# 03_Power.net
KiCad netlist of a schematic drawn in Altium Designer
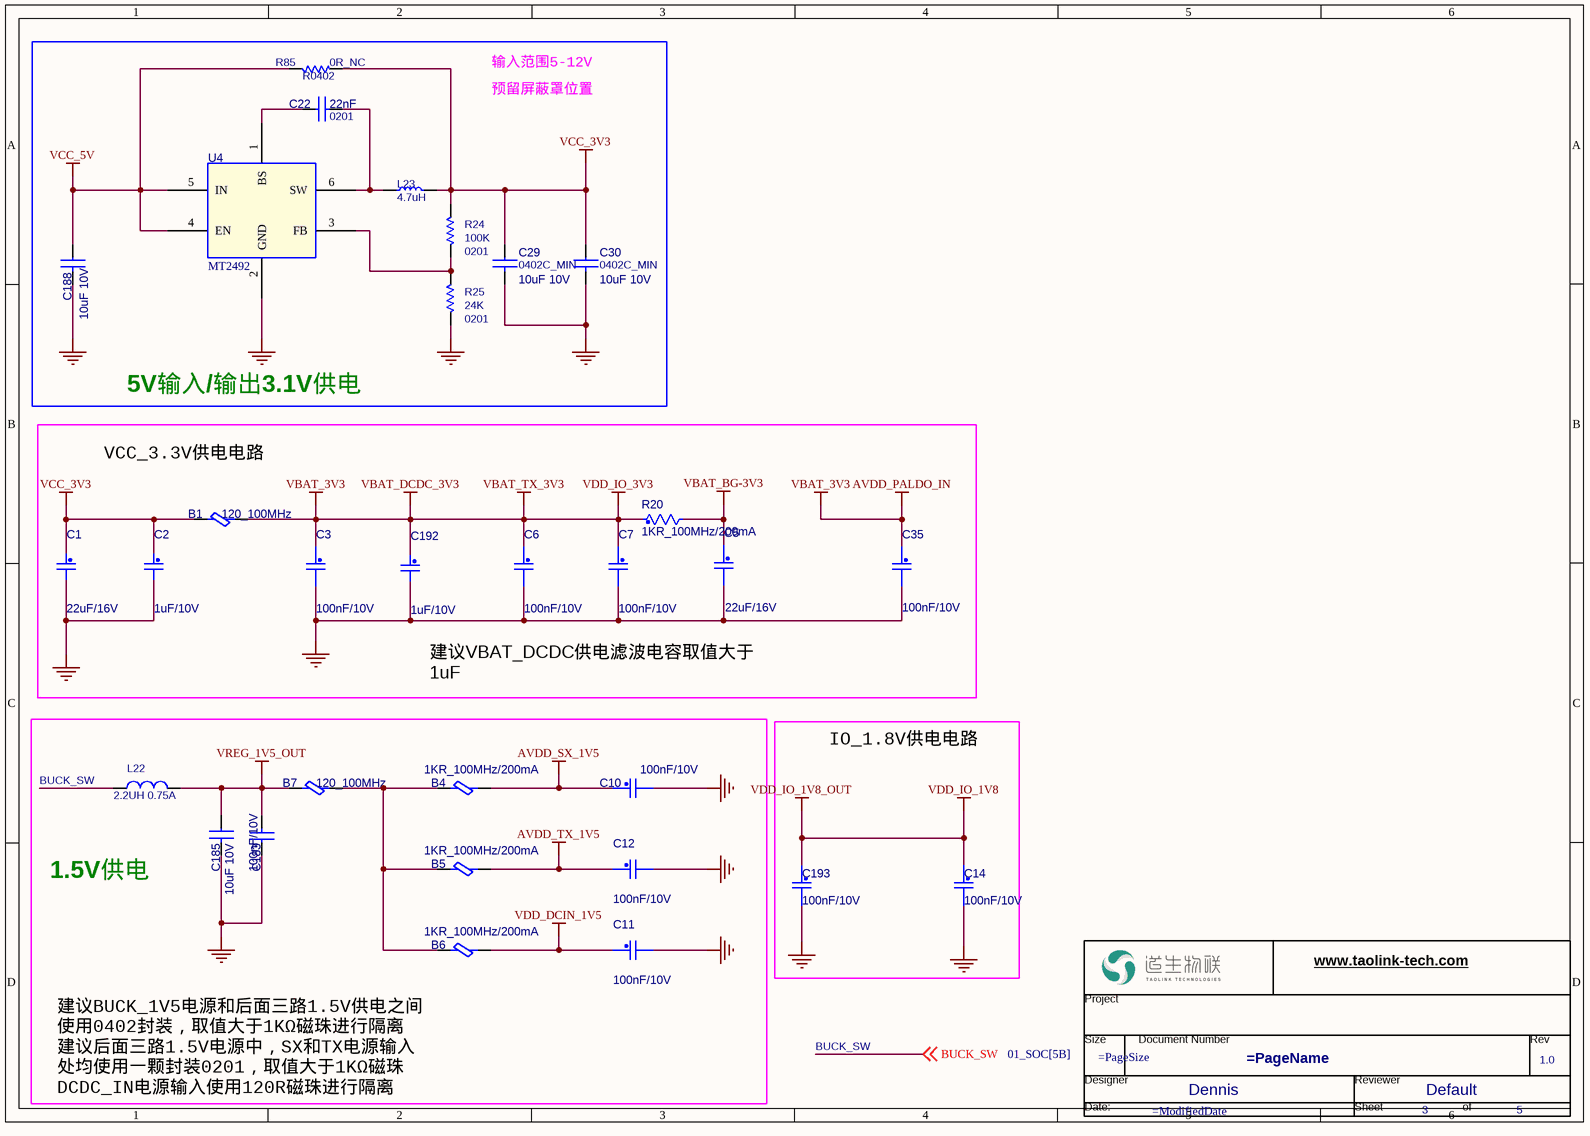
[diagram p0: 03_Power.SchDoc]

(export (version "E")
  (design (tool "Eeschema 10.0.6"))
  (components
    (comp (ref "B1")
      (value "120_100MHz")
      (footprint "l0402")
      (description "FERRITE CHIP 120 OHM 500MA 0402")
      (fields (field (name "EI PART#") "04_00075_01") (field (name "VENDOR PART#") "490-1005-1-ND"))
      (libsource (lib "*") (part "1212_BEAD_0"))
    )
    (comp (ref "B4")
      (value "1KR_100MHz/200mA")
      (footprint "0201")
      (description "FERRITE CHIP 120 OHM 500MA 0402")
      (fields (field (name "MANUFACTURE PART NUMBER") "BLM15AG121SN1D") (field (name "TOLERANCE") "25%"))
      (libsource (lib "*") (part "1212_BEAD_0"))
    )
    (comp (ref "B5")
      (value "1KR_100MHz/200mA")
      (footprint "0201")
      (description "FERRITE CHIP 120 OHM 500MA 0402")
      (fields (field (name "MANUFACTURE PART NUMBER") "BLM15AG121SN1D") (field (name "TOLERANCE") "25%"))
      (libsource (lib "*") (part "1212_BEAD_0"))
    )
    (comp (ref "B6")
      (value "1KR_100MHz/200mA")
      (footprint "0201")
      (description "FERRITE CHIP 120 OHM 500MA 0402")
      (fields (field (name "MANUFACTURE PART NUMBER") "BLM15AG121SN1D") (field (name "TOLERANCE") "25%"))
      (libsource (lib "*") (part "1212_BEAD_0"))
    )
    (comp (ref "B7")
      (value "120_100MHz")
      (footprint "l0402")
      (description "FERRITE CHIP 120 OHM 500MA 0402")
      (fields (field (name "MANUFACTURE PART NUMBER") "BLM15AG121SN1D") (field (name "TOLERANCE") "25%"))
      (libsource (lib "*") (part "1212_BEAD_0"))
    )
    (comp (ref "C1")
      (value "22uF/16V")
      (footprint "C0402")
      (description "Ceramic Capacitor, 10uF,+/-20%,X6S,16V,SMD,0603")
      (fields (field (name "MANUFACTURER") "Murata"))
      (libsource (lib "*") (part "Ceramic Capacitor"))
    )
    (comp (ref "C2")
      (value "1uF/10V")
      (footprint "0201")
      (description "Ceramic Capacitor,4.7uF 10V 0402,SUMSUNG")
      (fields (field (name "MANUFACTURER") "Samsung"))
      (libsource (lib "*") (part "Ceramic Capacitor"))
    )
    (comp (ref "C3")
      (value "100nF/10V")
      (footprint "0201")
      (description "Ceramic Capacitor,100nF,50V,+/-10%,X7R,0402,Fenghua")
      (fields (field (name "MANUFACTURER") "Fenghua"))
      (libsource (lib "*") (part "Ceramic Capacitor_14"))
    )
    (comp (ref "C5")
      (value "22uF/16V")
      (footprint "C0402")
      (description "Ceramic Capacitor,100nF,50V,+/-10%,X7R,0402,Fenghua")
      (fields (field (name "MANUFACTURER") "Fenghua"))
      (libsource (lib "*") (part "Ceramic Capacitor_14"))
    )
    (comp (ref "C6")
      (value "100nF/10V")
      (footprint "0201")
      (description "Ceramic Capacitor,100nF,50V,+/-10%,X7R,0402,Fenghua")
      (fields (field (name "MANUFACTURER") "Fenghua"))
      (libsource (lib "*") (part "Ceramic Capacitor_14"))
    )
    (comp (ref "C7")
      (value "100nF/10V")
      (footprint "0201")
      (description "Ceramic Capacitor,100nF,50V,+/-10%,X7R,0402,Fenghua")
      (fields (field (name "MANUFACTURER") "Fenghua"))
      (libsource (lib "*") (part "Ceramic Capacitor_14"))
    )
    (comp (ref "C10")
      (value "100nF/10V")
      (footprint "0201")
      (description "Ceramic Capacitor,100nF,50V,+/-10%,X7R,0402,Fenghua")
      (fields (field (name "MANUFACTURER") "Fenghua"))
      (libsource (lib "*") (part "Ceramic Capacitor_14"))
    )
    (comp (ref "C11")
      (value "100nF/10V")
      (footprint "0201")
      (description "Ceramic Capacitor,100nF,50V,+/-10%,X7R,0402,Fenghua")
      (fields (field (name "MANUFACTURER") "Fenghua"))
      (libsource (lib "*") (part "Ceramic Capacitor_14"))
    )
    (comp (ref "C12")
      (value "100nF/10V")
      (footprint "0201")
      (description "Ceramic Capacitor,100nF,50V,+/-10%,X7R,0402,Fenghua")
      (fields (field (name "MANUFACTURER") "Fenghua"))
      (libsource (lib "*") (part "Ceramic Capacitor_14"))
    )
    (comp (ref "C14")
      (value "100nF/10V")
      (footprint "0201")
      (description "Ceramic Capacitor,100nF,50V,+/-10%,X7R,0402,Fenghua")
      (fields (field (name "MANUFACTURER") "Fenghua"))
      (libsource (lib "*") (part "Ceramic Capacitor_14"))
    )
    (comp (ref "C22")
      (value "22nF")
      (footprint "0201")
      (fields (field (name "PCB FOOTPRINT") "0201"))
      (libsource (lib "*") (part "CAPACITOR NON-POL"))
    )
    (comp (ref "C29")
      (value "10uF 10V")
      (footprint "0402C_MIN")
      (fields (field (name "PCB FOOTPRINT") "0402C_MIN"))
      (libsource (lib "*") (part "CAPACITOR NON-POL"))
    )
    (comp (ref "C30")
      (value "10uF 10V")
      (footprint "0402C_MIN")
      (fields (field (name "PCB FOOTPRINT") "0402C_MIN"))
      (libsource (lib "*") (part "CAPACITOR NON-POL"))
    )
    (comp (ref "C35")
      (value "100nF/10V")
      (footprint "0201")
      (description "Ceramic Capacitor,100nF,50V,+/-10%,X7R,0402,Fenghua")
      (fields (field (name "MANUFACTURER") "Fenghua"))
      (libsource (lib "*") (part "Ceramic Capacitor_14"))
    )
    (comp (ref "C183") (value "100nF/10V") (footprint "0201") (libsource (lib "*") (part "CAP_NP")))
    (comp (ref "C185") (value "10uF 10V") (footprint "0402C_MIN") (libsource (lib "*") (part "CAP_NP")))
    (comp (ref "C188") (value "10uF 10V") (footprint "0402C_MIN") (libsource (lib "*") (part "CAP_NP")))
    (comp (ref "C192")
      (value "1uF/10V")
      (footprint "0201")
      (description "Ceramic Capacitor,4.7uF 10V 0402,SUMSUNG")
      (fields (field (name "MANUFACTURER") "Samsung"))
      (libsource (lib "*") (part "Ceramic Capacitor"))
    )
    (comp (ref "C193")
      (value "100nF/10V")
      (footprint "0201")
      (description "Ceramic Capacitor,100nF,50V,+/-10%,X7R,0402,Fenghua")
      (fields (field (name "MANUFACTURER") "Fenghua"))
      (libsource (lib "*") (part "Ceramic Capacitor_14"))
    )
    (comp (ref "L22")
      (value "2.2UH 0.75A")
      (footprint "C0603")
      (fields (field (name "REVIEWED2") "LBY"))
      (libsource (lib "*") (part "INDUCTOR_Dup2"))
    )
    (comp (ref "L23")
      (value "4.7uH")
      (footprint "R0603")
      (fields (field (name "REVIEWED") "LBY"))
      (libsource (lib "*") (part "INDUCTOR_Dup1"))
    )
    (comp (ref "R20")
      (value "1KR_100MHz/200mA")
      (footprint "0201")
      (description "Thick Film Resistor,0R,+/-5%,1/16W,-55°C ~ 155°C,SMD,0402,Fenghua")
      (fields (field (name "MANUFACTURER") "Fenghua"))
      (libsource (lib "*") (part "Resister"))
    )
    (comp (ref "R24")
      (value "100K")
      (footprint "0201")
      (fields (field (name "PCB FOOTPRINT") "0201"))
      (libsource (lib "*") (part "R"))
    )
    (comp (ref "R25")
      (value "24K")
      (footprint "0201")
      (fields (field (name "PCB FOOTPRINT") "0201"))
      (libsource (lib "*") (part "R"))
    )
    (comp (ref "R85")
      (value "0R_NC")
      (footprint "R0402")
      (fields (field (name "PCB FOOTPRINT") "R0402"))
      (libsource (lib "*") (part "R"))
    )
    (comp (ref "U4") (value "MT2492") (footprint "SOT23-6") (libsource (lib "*") (part "MT2492")))
  )
  (nets
    (net (code "1") (name "AVDD_PALDO_IN") (class "Default")
      (node (ref "B1") (pin "2") (pinfunction "2_2") (pintype "passive"))
      (node (ref "C192") (pin "1") (pinfunction "1_1") (pintype "passive"))
      (node (ref "C3") (pin "1") (pinfunction "1_1") (pintype "passive"))
      (node (ref "C35") (pin "1") (pinfunction "1_1") (pintype "passive"))
      (node (ref "C6") (pin "1") (pinfunction "1_1") (pintype "passive"))
      (node (ref "C7") (pin "1") (pinfunction "1_1") (pintype "passive"))
      (node (ref "R20") (pin "1") (pinfunction "1_1") (pintype "passive"))
    )
    (net (code "2") (name "AVDD_SX_1V5") (class "Default")
      (node (ref "B4") (pin "2") (pinfunction "2_2") (pintype "passive"))
      (node (ref "C10") (pin "1") (pinfunction "1_1") (pintype "passive"))
    )
    (net (code "3") (name "AVDD_TX_1V5") (class "Default")
      (node (ref "B5") (pin "2") (pinfunction "2_2") (pintype "passive"))
      (node (ref "C12") (pin "1") (pinfunction "1_1") (pintype "passive"))
    )
    (net (code "4") (name "BUCK_SW") (class "Default")
      (node (ref "L22") (pin "1") (pinfunction "1_1") (pintype "passive"))
    )
    (net (code "5") (name "GND") (class "Default")
      (node (ref "C1") (pin "2") (pinfunction "2_2") (pintype "passive"))
      (node (ref "C10") (pin "2") (pinfunction "2_2") (pintype "passive"))
      (node (ref "C11") (pin "2") (pinfunction "2_2") (pintype "passive"))
      (node (ref "C12") (pin "2") (pinfunction "2_2") (pintype "passive"))
      (node (ref "C14") (pin "2") (pinfunction "2_2") (pintype "passive"))
      (node (ref "C183") (pin "1") (pinfunction "1_1") (pintype "passive"))
      (node (ref "C185") (pin "2") (pinfunction "2_2") (pintype "passive"))
      (node (ref "C188") (pin "2") (pinfunction "2_2") (pintype "passive"))
      (node (ref "C192") (pin "2") (pinfunction "2_2") (pintype "passive"))
      (node (ref "C193") (pin "2") (pinfunction "2_2") (pintype "passive"))
      (node (ref "C2") (pin "2") (pinfunction "2_2") (pintype "passive"))
      (node (ref "C29") (pin "2") (pinfunction "2_2") (pintype "passive"))
      (node (ref "C3") (pin "2") (pinfunction "2_2") (pintype "passive"))
      (node (ref "C30") (pin "2") (pinfunction "2_2") (pintype "passive"))
      (node (ref "C35") (pin "2") (pinfunction "2_2") (pintype "passive"))
      (node (ref "C5") (pin "2") (pinfunction "2_2") (pintype "passive"))
      (node (ref "C6") (pin "2") (pinfunction "2_2") (pintype "passive"))
      (node (ref "C7") (pin "2") (pinfunction "2_2") (pintype "passive"))
      (node (ref "R25") (pin "2") (pinfunction "2_2") (pintype "passive"))
      (node (ref "U4") (pin "2") (pinfunction "GND_2") (pintype "passive"))
    )
    (net (code "6") (name "Net-(B4-Pad1)") (class "Default")
      (node (ref "B4") (pin "1") (pinfunction "1_1") (pintype "passive"))
      (node (ref "B5") (pin "1") (pinfunction "1_1") (pintype "passive"))
      (node (ref "B6") (pin "1") (pinfunction "1_1") (pintype "passive"))
      (node (ref "B7") (pin "2") (pinfunction "2_2") (pintype "passive"))
    )
    (net (code "7") (name "Net-(U4-BS)") (class "Default")
      (node (ref "C22") (pin "1") (pinfunction "1_1") (pintype "passive"))
      (node (ref "U4") (pin "1") (pinfunction "BS_1") (pintype "passive"))
    )
    (net (code "8") (name "Net-(U4-FB)") (class "Default")
      (node (ref "R24") (pin "2") (pinfunction "2_2") (pintype "passive"))
      (node (ref "R25") (pin "1") (pinfunction "1_1") (pintype "passive"))
      (node (ref "U4") (pin "3") (pinfunction "FB_3") (pintype "passive"))
    )
    (net (code "9") (name "Net-(U4-SW)") (class "Default")
      (node (ref "C22") (pin "2") (pinfunction "2_2") (pintype "passive"))
      (node (ref "L23") (pin "1") (pinfunction "1_1") (pintype "passive"))
      (node (ref "U4") (pin "6") (pinfunction "SW_6") (pintype "passive"))
    )
    (net (code "10") (name "VBAT_BG-3V3") (class "Default")
      (node (ref "C5") (pin "1") (pinfunction "1_1") (pintype "passive"))
      (node (ref "R20") (pin "2") (pinfunction "2_2") (pintype "passive"))
    )
    (net (code "11") (name "VCC_3V3") (class "Default")
      (node (ref "B1") (pin "1") (pinfunction "1_1") (pintype "passive"))
      (node (ref "C1") (pin "1") (pinfunction "1_1") (pintype "passive"))
      (node (ref "C2") (pin "1") (pinfunction "1_1") (pintype "passive"))
      (node (ref "C29") (pin "1") (pinfunction "1_1") (pintype "passive"))
      (node (ref "C30") (pin "1") (pinfunction "1_1") (pintype "passive"))
      (node (ref "L23") (pin "2") (pinfunction "2_2") (pintype "passive"))
      (node (ref "R24") (pin "1") (pinfunction "1_1") (pintype "passive"))
      (node (ref "R85") (pin "2") (pinfunction "2_2") (pintype "passive"))
    )
    (net (code "12") (name "VCC_5V") (class "Default")
      (node (ref "C188") (pin "1") (pinfunction "1_1") (pintype "passive"))
      (node (ref "R85") (pin "1") (pinfunction "1_1") (pintype "passive"))
      (node (ref "U4") (pin "4") (pinfunction "EN_4") (pintype "passive"))
      (node (ref "U4") (pin "5") (pinfunction "IN_5") (pintype "passive"))
    )
    (net (code "13") (name "VDD_DCIN_1V5") (class "Default")
      (node (ref "B6") (pin "2") (pinfunction "2_2") (pintype "passive"))
      (node (ref "C11") (pin "1") (pinfunction "1_1") (pintype "passive"))
    )
    (net (code "14") (name "VDD_IO_1V8") (class "Default")
      (node (ref "C14") (pin "1") (pinfunction "1_1") (pintype "passive"))
      (node (ref "C193") (pin "1") (pinfunction "1_1") (pintype "passive"))
    )
    (net (code "15") (name "VREG_1V5_OUT") (class "Default")
      (node (ref "B7") (pin "1") (pinfunction "1_1") (pintype "passive"))
      (node (ref "C183") (pin "2") (pinfunction "2_2") (pintype "passive"))
      (node (ref "C185") (pin "1") (pinfunction "1_1") (pintype "passive"))
      (node (ref "L22") (pin "2") (pinfunction "2_2") (pintype "passive"))
    )
  )
)
